# Schematic_for_AT-AT_v2.net
KiCad netlist of a schematic drawn in EAGLE
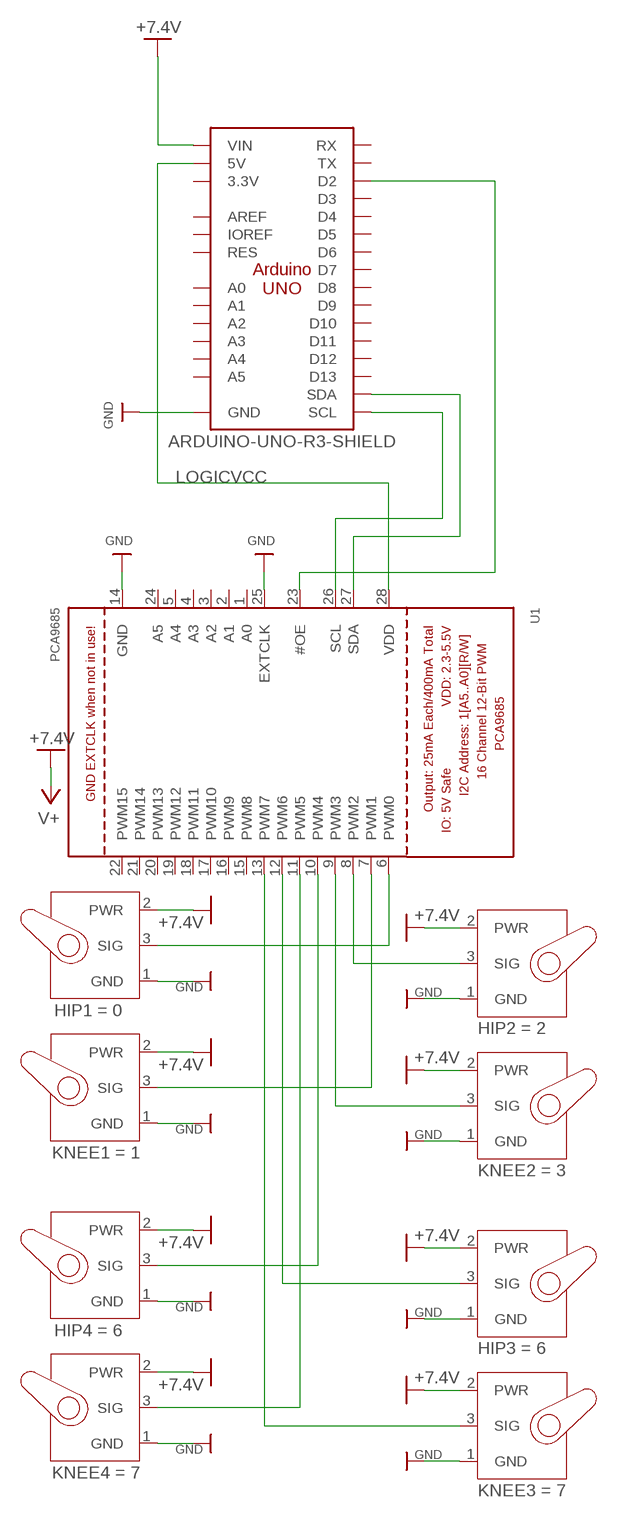
[diagram p0: schematic, sheet 1]
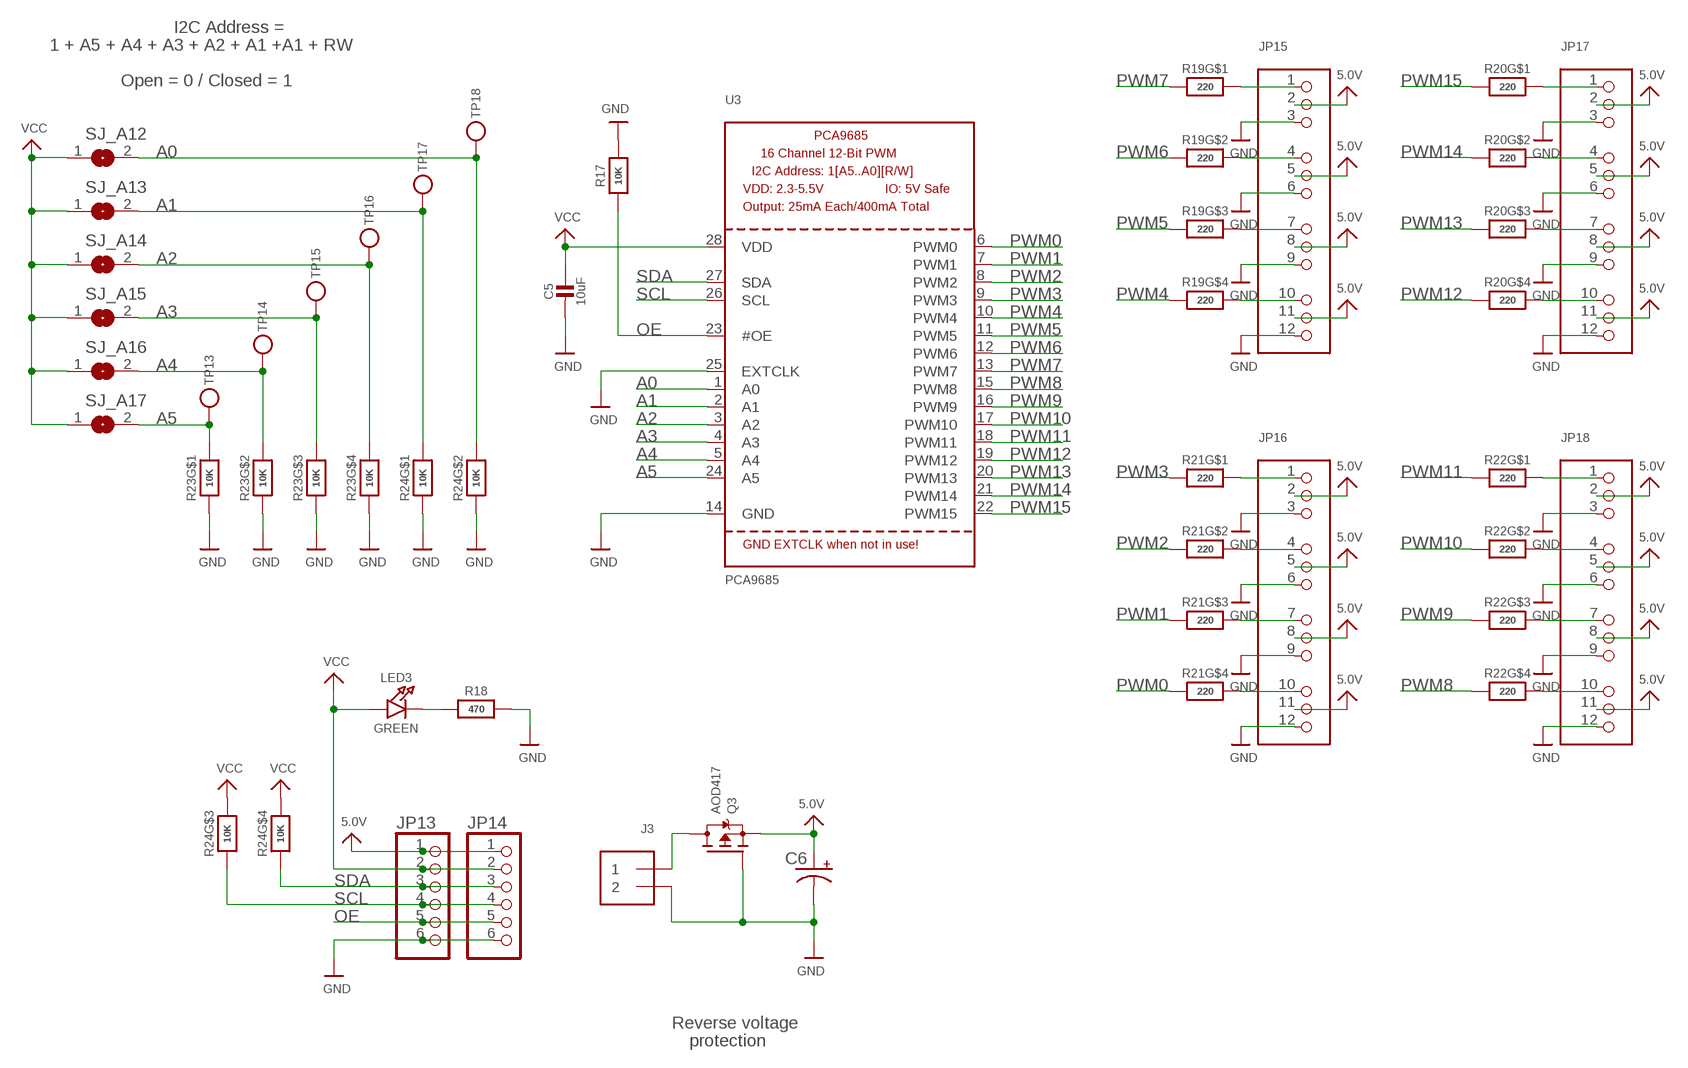
[diagram p1: schematic, sheet 2]

(export (version "E")
  (design (tool "Eeschema 10.0.6"))
  (components
    (comp (ref "U$1")
      (value "SERVOSG90-HDR")
      (footprint "eagle-import:1X03")
      (fields (field (name "HIP2") "2"))
      (libsource (lib "eagle-import") (part "SERVOSG90-HDR"))
    )
    (comp (ref "U$2")
      (value "SERVOSG90-HDR")
      (footprint "eagle-import:1X03")
      (fields (field (name "KNEE2") "3"))
      (libsource (lib "eagle-import") (part "SERVOSG90-HDR"))
    )
    (comp (ref "U$3")
      (value "SERVOSG90-HDR")
      (footprint "eagle-import:1X03")
      (fields (field (name "HIP3") "6"))
      (libsource (lib "eagle-import") (part "SERVOSG90-HDR"))
    )
    (comp (ref "U$4")
      (value "SERVOSG90-HDR")
      (footprint "eagle-import:1X03")
      (fields (field (name "KNEE3") "7"))
      (libsource (lib "eagle-import") (part "SERVOSG90-HDR"))
    )
    (comp (ref "U$5")
      (value "SERVOSG90-HDR")
      (footprint "eagle-import:1X03")
      (fields (field (name "HIP1") "0"))
      (libsource (lib "eagle-import") (part "SERVOSG90-HDR"))
    )
    (comp (ref "U$6")
      (value "SERVOSG90-HDR")
      (footprint "eagle-import:1X03")
      (fields (field (name "KNEE1") "1"))
      (libsource (lib "eagle-import") (part "SERVOSG90-HDR"))
    )
    (comp (ref "U$7")
      (value "SERVOSG90-HDR")
      (footprint "eagle-import:1X03")
      (fields (field (name "HIP4") "6"))
      (libsource (lib "eagle-import") (part "SERVOSG90-HDR"))
    )
    (comp (ref "U$8")
      (value "SERVOSG90-HDR")
      (footprint "eagle-import:1X03")
      (fields (field (name "KNEE4") "7"))
      (libsource (lib "eagle-import") (part "SERVOSG90-HDR"))
    )
    (comp (ref "U$9")
      (value "ARDUINO-UNO-R3-SHIELD")
      (footprint "eagle-import:ARDUINO-UNO-R3-SHIELD")
      (libsource (lib "eagle-import") (part "ARDUINO-UNO-R3-SHIELD"))
    )
    (comp (ref "U1")
      (value "PCA9685")
      (footprint "eagle-import:TSSOP28")
      (libsource (lib "eagle-import") (part "PCA9685"))
    )
    (comp (ref "C5")
      (value "10uF")
      (footprint "eagle-import:0805-NO")
      (libsource (lib "eagle-import") (part "CAP_CERAMIC0805-NOOUTLINE"))
    )
    (comp (ref "C6")
      (value "CPOL-USE3.5-8")
      (footprint "eagle-import:E3,5-8")
      (libsource (lib "eagle-import") (part "CPOL-USE3.5-8"))
    )
    (comp (ref "J3")
      (value "TERMBLOCK_1X2")
      (footprint "eagle-import:TERMBLOCK_1X2-3.5MM")
      (libsource (lib "eagle-import") (part "TERMBLOCK_1X2"))
    )
    (comp (ref "JP13")
      (value "PINHD-1X6CB")
      (footprint "eagle-import:1X06-CLEANBIG")
      (libsource (lib "eagle-import") (part "PINHD-1X6CB"))
    )
    (comp (ref "JP14")
      (value "PINHD-1X6CB")
      (footprint "eagle-import:1X06-CLEANBIG")
      (libsource (lib "eagle-import") (part "PINHD-1X6CB"))
    )
    (comp (ref "JP15")
      (value "HEADER-3X04")
      (footprint "eagle-import:3X04")
      (libsource (lib "eagle-import") (part "HEADER-3X04"))
    )
    (comp (ref "JP16")
      (value "HEADER-3X04")
      (footprint "eagle-import:3X04")
      (libsource (lib "eagle-import") (part "HEADER-3X04"))
    )
    (comp (ref "JP17")
      (value "HEADER-3X04")
      (footprint "eagle-import:3X04")
      (libsource (lib "eagle-import") (part "HEADER-3X04"))
    )
    (comp (ref "JP18")
      (value "HEADER-3X04")
      (footprint "eagle-import:3X04")
      (libsource (lib "eagle-import") (part "HEADER-3X04"))
    )
    (comp (ref "LED3")
      (value "GREEN")
      (footprint "eagle-import:CHIPLED_0805_NOOUTLINE")
      (libsource (lib "eagle-import") (part "LED0805_NOOUTLINE"))
    )
    (comp (ref "Q3")
      (value "AOD417")
      (footprint "eagle-import:TO252")
      (libsource (lib "eagle-import") (part "MOSFET-PTO252"))
    )
    (comp (ref "R17")
      (value "10K")
      (footprint "eagle-import:0805-NO")
      (libsource (lib "eagle-import") (part "RESISTOR0805_NOOUTLINE"))
    )
    (comp (ref "R18")
      (value "470")
      (footprint "eagle-import:_0805MP")
      (libsource (lib "eagle-import") (part "RESISTOR_0805MP"))
    )
    (comp (ref "R19")
      (value "220")
      (footprint "eagle-import:RESPACK_4X0603")
      (libsource (lib "eagle-import") (part "RESISTOR_4PACK"))
    )
    (comp (ref "R20")
      (value "220")
      (footprint "eagle-import:RESPACK_4X0603")
      (libsource (lib "eagle-import") (part "RESISTOR_4PACK"))
    )
    (comp (ref "R21")
      (value "220")
      (footprint "eagle-import:RESPACK_4X0603")
      (libsource (lib "eagle-import") (part "RESISTOR_4PACK"))
    )
    (comp (ref "R22")
      (value "220")
      (footprint "eagle-import:RESPACK_4X0603")
      (libsource (lib "eagle-import") (part "RESISTOR_4PACK"))
    )
    (comp (ref "R23")
      (value "10K")
      (footprint "eagle-import:RESPACK_4X0603")
      (libsource (lib "eagle-import") (part "RESISTOR_4PACK"))
    )
    (comp (ref "R24")
      (value "10K")
      (footprint "eagle-import:RESPACK_4X0603")
      (libsource (lib "eagle-import") (part "RESISTOR_4PACK"))
    )
    (comp (ref "SJ_A12")
      (value "SOLDERJUMPERREFLOW_NOPASTE")
      (footprint "eagle-import:SOLDERJUMPER_REFLOW_NOPASTE")
      (libsource (lib "eagle-import") (part "SOLDERJUMPERREFLOW_NOPASTE"))
    )
    (comp (ref "SJ_A13")
      (value "SOLDERJUMPERREFLOW_NOPASTE")
      (footprint "eagle-import:SOLDERJUMPER_REFLOW_NOPASTE")
      (libsource (lib "eagle-import") (part "SOLDERJUMPERREFLOW_NOPASTE"))
    )
    (comp (ref "SJ_A14")
      (value "SOLDERJUMPERREFLOW_NOPASTE")
      (footprint "eagle-import:SOLDERJUMPER_REFLOW_NOPASTE")
      (libsource (lib "eagle-import") (part "SOLDERJUMPERREFLOW_NOPASTE"))
    )
    (comp (ref "SJ_A15")
      (value "SOLDERJUMPERREFLOW_NOPASTE")
      (footprint "eagle-import:SOLDERJUMPER_REFLOW_NOPASTE")
      (libsource (lib "eagle-import") (part "SOLDERJUMPERREFLOW_NOPASTE"))
    )
    (comp (ref "SJ_A16")
      (value "SOLDERJUMPERREFLOW_NOPASTE")
      (footprint "eagle-import:SOLDERJUMPER_REFLOW_NOPASTE")
      (libsource (lib "eagle-import") (part "SOLDERJUMPERREFLOW_NOPASTE"))
    )
    (comp (ref "SJ_A17")
      (value "SOLDERJUMPERREFLOW_NOPASTE")
      (footprint "eagle-import:SOLDERJUMPER_REFLOW_NOPASTE")
      (libsource (lib "eagle-import") (part "SOLDERJUMPERREFLOW_NOPASTE"))
    )
    (comp (ref "TP13")
      (value "TESTPOINTROUND1MM")
      (footprint "eagle-import:TESTPOINT_ROUND_1MM")
      (libsource (lib "eagle-import") (part "TESTPOINTROUND1MM"))
    )
    (comp (ref "TP14")
      (value "TESTPOINTROUND1MM")
      (footprint "eagle-import:TESTPOINT_ROUND_1MM")
      (libsource (lib "eagle-import") (part "TESTPOINTROUND1MM"))
    )
    (comp (ref "TP15")
      (value "TESTPOINTROUND1MM")
      (footprint "eagle-import:TESTPOINT_ROUND_1MM")
      (libsource (lib "eagle-import") (part "TESTPOINTROUND1MM"))
    )
    (comp (ref "TP16")
      (value "TESTPOINTROUND1MM")
      (footprint "eagle-import:TESTPOINT_ROUND_1MM")
      (libsource (lib "eagle-import") (part "TESTPOINTROUND1MM"))
    )
    (comp (ref "TP17")
      (value "TESTPOINTROUND1MM")
      (footprint "eagle-import:TESTPOINT_ROUND_1MM")
      (libsource (lib "eagle-import") (part "TESTPOINTROUND1MM"))
    )
    (comp (ref "TP18")
      (value "TESTPOINTROUND1MM")
      (footprint "eagle-import:TESTPOINT_ROUND_1MM")
      (libsource (lib "eagle-import") (part "TESTPOINTROUND1MM"))
    )
    (comp (ref "U3")
      (value "PCA9685")
      (footprint "eagle-import:TSSOP28")
      (libsource (lib "eagle-import") (part "PCA9685"))
    )
  )
  (nets
    (net (code "1") (name "+7.4V") (class "Default")
      (node (ref "U$1") (pin "2") (pinfunction "PWR_2") (pintype "bidirectional"))
      (node (ref "U$2") (pin "2") (pinfunction "PWR_2") (pintype "bidirectional"))
      (node (ref "U$3") (pin "2") (pinfunction "PWR_2") (pintype "bidirectional"))
      (node (ref "U$4") (pin "2") (pinfunction "PWR_2") (pintype "bidirectional"))
      (node (ref "U$5") (pin "2") (pinfunction "PWR_2") (pintype "bidirectional"))
      (node (ref "U$6") (pin "2") (pinfunction "PWR_2") (pintype "bidirectional"))
      (node (ref "U$7") (pin "2") (pinfunction "PWR_2") (pintype "bidirectional"))
      (node (ref "U$8") (pin "2") (pinfunction "PWR_2") (pintype "bidirectional"))
      (node (ref "U$9") (pin "VIN") (pinfunction "VIN_VIN") (pintype "bidirectional"))
    )
    (net (code "2") (name "5.0V") (class "Default")
      (node (ref "C6") (pin "+") (pinfunction "+_+") (pintype "passive"))
      (node (ref "JP13") (pin "1") (pinfunction "1_1") (pintype "passive"))
      (node (ref "JP14") (pin "1") (pinfunction "1_1") (pintype "passive"))
      (node (ref "JP15") (pin "11") (pinfunction "11_11") (pintype "passive"))
      (node (ref "JP15") (pin "2") (pinfunction "2_2") (pintype "passive"))
      (node (ref "JP15") (pin "5") (pinfunction "5_5") (pintype "passive"))
      (node (ref "JP15") (pin "8") (pinfunction "8_8") (pintype "passive"))
      (node (ref "JP16") (pin "11") (pinfunction "11_11") (pintype "passive"))
      (node (ref "JP16") (pin "2") (pinfunction "2_2") (pintype "passive"))
      (node (ref "JP16") (pin "5") (pinfunction "5_5") (pintype "passive"))
      (node (ref "JP16") (pin "8") (pinfunction "8_8") (pintype "passive"))
      (node (ref "JP17") (pin "11") (pinfunction "11_11") (pintype "passive"))
      (node (ref "JP17") (pin "2") (pinfunction "2_2") (pintype "passive"))
      (node (ref "JP17") (pin "5") (pinfunction "5_5") (pintype "passive"))
      (node (ref "JP17") (pin "8") (pinfunction "8_8") (pintype "passive"))
      (node (ref "JP18") (pin "11") (pinfunction "11_11") (pintype "passive"))
      (node (ref "JP18") (pin "2") (pinfunction "2_2") (pintype "passive"))
      (node (ref "JP18") (pin "5") (pinfunction "5_5") (pintype "passive"))
      (node (ref "JP18") (pin "8") (pinfunction "8_8") (pintype "passive"))
      (node (ref "Q3") (pin "2") (pinfunction "S_2") (pintype "passive"))
    )
    (net (code "3") (name "A0") (class "Default")
      (node (ref "R24") (pin "7") (pinfunction "2_7") (pintype "passive"))
      (node (ref "SJ_A12") (pin "2") (pinfunction "2_2") (pintype "passive"))
      (node (ref "TP18") (pin "P$1") (pinfunction "P$1_P$1") (pintype "bidirectional"))
      (node (ref "U3") (pin "1") (pinfunction "A0_1") (pintype "bidirectional"))
    )
    (net (code "4") (name "A1") (class "Default")
      (node (ref "R24") (pin "8") (pinfunction "2_8") (pintype "passive"))
      (node (ref "SJ_A13") (pin "2") (pinfunction "2_2") (pintype "passive"))
      (node (ref "TP17") (pin "P$1") (pinfunction "P$1_P$1") (pintype "bidirectional"))
      (node (ref "U3") (pin "2") (pinfunction "A1_2") (pintype "bidirectional"))
    )
    (net (code "5") (name "A2") (class "Default")
      (node (ref "R23") (pin "5") (pinfunction "2_5") (pintype "passive"))
      (node (ref "SJ_A14") (pin "2") (pinfunction "2_2") (pintype "passive"))
      (node (ref "TP16") (pin "P$1") (pinfunction "P$1_P$1") (pintype "bidirectional"))
      (node (ref "U3") (pin "3") (pinfunction "A2_3") (pintype "bidirectional"))
    )
    (net (code "6") (name "A3") (class "Default")
      (node (ref "R23") (pin "6") (pinfunction "2_6") (pintype "passive"))
      (node (ref "SJ_A15") (pin "2") (pinfunction "2_2") (pintype "passive"))
      (node (ref "TP15") (pin "P$1") (pinfunction "P$1_P$1") (pintype "bidirectional"))
      (node (ref "U3") (pin "4") (pinfunction "A3_4") (pintype "bidirectional"))
    )
    (net (code "7") (name "A4") (class "Default")
      (node (ref "R23") (pin "7") (pinfunction "2_7") (pintype "passive"))
      (node (ref "SJ_A16") (pin "2") (pinfunction "2_2") (pintype "passive"))
      (node (ref "TP14") (pin "P$1") (pinfunction "P$1_P$1") (pintype "bidirectional"))
      (node (ref "U3") (pin "5") (pinfunction "A4_5") (pintype "bidirectional"))
    )
    (net (code "8") (name "A5") (class "Default")
      (node (ref "R23") (pin "8") (pinfunction "2_8") (pintype "passive"))
      (node (ref "SJ_A17") (pin "2") (pinfunction "2_2") (pintype "passive"))
      (node (ref "TP13") (pin "P$1") (pinfunction "P$1_P$1") (pintype "bidirectional"))
      (node (ref "U3") (pin "24") (pinfunction "A5_24") (pintype "bidirectional"))
    )
    (net (code "9") (name "GND") (class "Default")
      (node (ref "C5") (pin "2") (pinfunction "2_2") (pintype "passive"))
      (node (ref "C6") (pin "-") (pinfunction "-_-") (pintype "passive"))
      (node (ref "J3") (pin "2") (pinfunction "2_2") (pintype "passive"))
      (node (ref "JP13") (pin "6") (pinfunction "6_6") (pintype "passive"))
      (node (ref "JP14") (pin "6") (pinfunction "6_6") (pintype "passive"))
      (node (ref "JP15") (pin "12") (pinfunction "12_12") (pintype "passive"))
      (node (ref "JP15") (pin "3") (pinfunction "3_3") (pintype "passive"))
      (node (ref "JP15") (pin "6") (pinfunction "6_6") (pintype "passive"))
      (node (ref "JP15") (pin "9") (pinfunction "9_9") (pintype "passive"))
      (node (ref "JP16") (pin "12") (pinfunction "12_12") (pintype "passive"))
      (node (ref "JP16") (pin "3") (pinfunction "3_3") (pintype "passive"))
      (node (ref "JP16") (pin "6") (pinfunction "6_6") (pintype "passive"))
      (node (ref "JP16") (pin "9") (pinfunction "9_9") (pintype "passive"))
      (node (ref "JP17") (pin "12") (pinfunction "12_12") (pintype "passive"))
      (node (ref "JP17") (pin "3") (pinfunction "3_3") (pintype "passive"))
      (node (ref "JP17") (pin "6") (pinfunction "6_6") (pintype "passive"))
      (node (ref "JP17") (pin "9") (pinfunction "9_9") (pintype "passive"))
      (node (ref "JP18") (pin "12") (pinfunction "12_12") (pintype "passive"))
      (node (ref "JP18") (pin "3") (pinfunction "3_3") (pintype "passive"))
      (node (ref "JP18") (pin "6") (pinfunction "6_6") (pintype "passive"))
      (node (ref "JP18") (pin "9") (pinfunction "9_9") (pintype "passive"))
      (node (ref "Q3") (pin "1") (pinfunction "G_1") (pintype "passive"))
      (node (ref "R17") (pin "2") (pinfunction "2_2") (pintype "passive"))
      (node (ref "R18") (pin "2") (pinfunction "2_2") (pintype "passive"))
      (node (ref "R23") (pin "1") (pinfunction "1_1") (pintype "passive"))
      (node (ref "R23") (pin "2") (pinfunction "1_2") (pintype "passive"))
      (node (ref "R23") (pin "3") (pinfunction "1_3") (pintype "passive"))
      (node (ref "R23") (pin "4") (pinfunction "1_4") (pintype "passive"))
      (node (ref "R24") (pin "1") (pinfunction "1_1") (pintype "passive"))
      (node (ref "R24") (pin "2") (pinfunction "1_2") (pintype "passive"))
      (node (ref "U$1") (pin "1") (pinfunction "GND_1") (pintype "bidirectional"))
      (node (ref "U$2") (pin "1") (pinfunction "GND_1") (pintype "bidirectional"))
      (node (ref "U$3") (pin "1") (pinfunction "GND_1") (pintype "bidirectional"))
      (node (ref "U$4") (pin "1") (pinfunction "GND_1") (pintype "bidirectional"))
      (node (ref "U$5") (pin "1") (pinfunction "GND_1") (pintype "bidirectional"))
      (node (ref "U$6") (pin "1") (pinfunction "GND_1") (pintype "bidirectional"))
      (node (ref "U$7") (pin "1") (pinfunction "GND_1") (pintype "bidirectional"))
      (node (ref "U$8") (pin "1") (pinfunction "GND_1") (pintype "bidirectional"))
      (node (ref "U$9") (pin "GND@0") (pinfunction "GND_GND@0") (pintype "bidirectional"))
      (node (ref "U$9") (pin "GND@1") (pinfunction "GND_GND@1") (pintype "bidirectional"))
      (node (ref "U$9") (pin "GND@2") (pinfunction "GND_GND@2") (pintype "bidirectional"))
      (node (ref "U1") (pin "14") (pinfunction "GND_14") (pintype "power_in"))
      (node (ref "U1") (pin "25") (pinfunction "EXTCLK_25") (pintype "input"))
      (node (ref "U3") (pin "14") (pinfunction "GND_14") (pintype "power_in"))
      (node (ref "U3") (pin "25") (pinfunction "EXTCLK_25") (pintype "input"))
    )
    (net (code "10") (name "LOGICVCC") (class "Default")
      (node (ref "U$9") (pin "5V") (pinfunction "5V_5V") (pintype "bidirectional"))
      (node (ref "U1") (pin "28") (pinfunction "VDD_28") (pintype "power_in"))
    )
    (net (code "11") (name "Net-(LED3-PadC)") (class "Default")
      (node (ref "LED3") (pin "C") (pinfunction "C_C") (pintype "passive"))
      (node (ref "R18") (pin "1") (pinfunction "1_1") (pintype "passive"))
    )
    (net (code "12") (name "Net-(Q3-D)") (class "Default")
      (node (ref "J3") (pin "1") (pinfunction "1_1") (pintype "passive"))
      (node (ref "Q3") (pin "3") (pinfunction "D_3") (pintype "passive"))
    )
    (net (code "13") (name "Net-(R19A-2)") (class "Default")
      (node (ref "JP15") (pin "1") (pinfunction "1_1") (pintype "passive"))
      (node (ref "R19") (pin "8") (pinfunction "2_8") (pintype "passive"))
    )
    (net (code "14") (name "Net-(R19B-2)") (class "Default")
      (node (ref "JP15") (pin "4") (pinfunction "4_4") (pintype "passive"))
      (node (ref "R19") (pin "7") (pinfunction "2_7") (pintype "passive"))
    )
    (net (code "15") (name "Net-(R19C-2)") (class "Default")
      (node (ref "JP15") (pin "7") (pinfunction "7_7") (pintype "passive"))
      (node (ref "R19") (pin "6") (pinfunction "2_6") (pintype "passive"))
    )
    (net (code "16") (name "Net-(R19D-2)") (class "Default")
      (node (ref "JP15") (pin "10") (pinfunction "10_10") (pintype "passive"))
      (node (ref "R19") (pin "5") (pinfunction "2_5") (pintype "passive"))
    )
    (net (code "17") (name "Net-(R20A-2)") (class "Default")
      (node (ref "JP17") (pin "1") (pinfunction "1_1") (pintype "passive"))
      (node (ref "R20") (pin "8") (pinfunction "2_8") (pintype "passive"))
    )
    (net (code "18") (name "Net-(R20B-2)") (class "Default")
      (node (ref "JP17") (pin "4") (pinfunction "4_4") (pintype "passive"))
      (node (ref "R20") (pin "7") (pinfunction "2_7") (pintype "passive"))
    )
    (net (code "19") (name "Net-(R20C-2)") (class "Default")
      (node (ref "JP17") (pin "7") (pinfunction "7_7") (pintype "passive"))
      (node (ref "R20") (pin "6") (pinfunction "2_6") (pintype "passive"))
    )
    (net (code "20") (name "Net-(R20D-2)") (class "Default")
      (node (ref "JP17") (pin "10") (pinfunction "10_10") (pintype "passive"))
      (node (ref "R20") (pin "5") (pinfunction "2_5") (pintype "passive"))
    )
    (net (code "21") (name "Net-(R21A-2)") (class "Default")
      (node (ref "JP16") (pin "1") (pinfunction "1_1") (pintype "passive"))
      (node (ref "R21") (pin "8") (pinfunction "2_8") (pintype "passive"))
    )
    (net (code "22") (name "Net-(R21B-2)") (class "Default")
      (node (ref "JP16") (pin "4") (pinfunction "4_4") (pintype "passive"))
      (node (ref "R21") (pin "7") (pinfunction "2_7") (pintype "passive"))
    )
    (net (code "23") (name "Net-(R21C-2)") (class "Default")
      (node (ref "JP16") (pin "7") (pinfunction "7_7") (pintype "passive"))
      (node (ref "R21") (pin "6") (pinfunction "2_6") (pintype "passive"))
    )
    (net (code "24") (name "Net-(R21D-2)") (class "Default")
      (node (ref "JP16") (pin "10") (pinfunction "10_10") (pintype "passive"))
      (node (ref "R21") (pin "5") (pinfunction "2_5") (pintype "passive"))
    )
    (net (code "25") (name "Net-(R22A-2)") (class "Default")
      (node (ref "JP18") (pin "1") (pinfunction "1_1") (pintype "passive"))
      (node (ref "R22") (pin "8") (pinfunction "2_8") (pintype "passive"))
    )
    (net (code "26") (name "Net-(R22B-2)") (class "Default")
      (node (ref "JP18") (pin "4") (pinfunction "4_4") (pintype "passive"))
      (node (ref "R22") (pin "7") (pinfunction "2_7") (pintype "passive"))
    )
    (net (code "27") (name "Net-(R22C-2)") (class "Default")
      (node (ref "JP18") (pin "7") (pinfunction "7_7") (pintype "passive"))
      (node (ref "R22") (pin "6") (pinfunction "2_6") (pintype "passive"))
    )
    (net (code "28") (name "Net-(R22D-2)") (class "Default")
      (node (ref "JP18") (pin "10") (pinfunction "10_10") (pintype "passive"))
      (node (ref "R22") (pin "5") (pinfunction "2_5") (pintype "passive"))
    )
    (net (code "29") (name "Net-(U$1-SIG)") (class "Default")
      (node (ref "U$1") (pin "3") (pinfunction "SIG_3") (pintype "bidirectional"))
      (node (ref "U1") (pin "8") (pinfunction "PWM2_8") (pintype "output"))
    )
    (net (code "30") (name "Net-(U$2-SIG)") (class "Default")
      (node (ref "U$2") (pin "3") (pinfunction "SIG_3") (pintype "bidirectional"))
      (node (ref "U1") (pin "9") (pinfunction "PWM3_9") (pintype "output"))
    )
    (net (code "31") (name "Net-(U$3-SIG)") (class "Default")
      (node (ref "U$3") (pin "3") (pinfunction "SIG_3") (pintype "bidirectional"))
      (node (ref "U1") (pin "12") (pinfunction "PWM6_12") (pintype "output"))
    )
    (net (code "32") (name "Net-(U$4-SIG)") (class "Default")
      (node (ref "U$4") (pin "3") (pinfunction "SIG_3") (pintype "bidirectional"))
      (node (ref "U1") (pin "13") (pinfunction "PWM7_13") (pintype "output"))
    )
    (net (code "33") (name "Net-(U$5-SIG)") (class "Default")
      (node (ref "U$5") (pin "3") (pinfunction "SIG_3") (pintype "bidirectional"))
      (node (ref "U1") (pin "6") (pinfunction "PWM0_6") (pintype "output"))
    )
    (net (code "34") (name "Net-(U$6-SIG)") (class "Default")
      (node (ref "U$6") (pin "3") (pinfunction "SIG_3") (pintype "bidirectional"))
      (node (ref "U1") (pin "7") (pinfunction "PWM1_7") (pintype "output"))
    )
    (net (code "35") (name "Net-(U$7-SIG)") (class "Default")
      (node (ref "U$7") (pin "3") (pinfunction "SIG_3") (pintype "bidirectional"))
      (node (ref "U1") (pin "10") (pinfunction "PWM4_10") (pintype "output"))
    )
    (net (code "36") (name "Net-(U$8-SIG)") (class "Default")
      (node (ref "U$8") (pin "3") (pinfunction "SIG_3") (pintype "bidirectional"))
      (node (ref "U1") (pin "11") (pinfunction "PWM5_11") (pintype "output"))
    )
    (net (code "37") (name "Net-(U1-#OE)") (class "Default")
      (node (ref "U$9") (pin "D2") (pinfunction "D2_D2") (pintype "bidirectional"))
      (node (ref "U1") (pin "23") (pinfunction "#OE_23") (pintype "input"))
    )
    (net (code "38") (name "Net-(U1-SCL)") (class "Default")
      (node (ref "U$9") (pin "SCL") (pinfunction "SCL_SCL") (pintype "bidirectional"))
      (node (ref "U1") (pin "26") (pinfunction "SCL_26") (pintype "bidirectional"))
    )
    (net (code "39") (name "Net-(U1-SDA)") (class "Default")
      (node (ref "U$9") (pin "SDA") (pinfunction "SDA_SDA") (pintype "bidirectional"))
      (node (ref "U1") (pin "27") (pinfunction "SDA_27") (pintype "bidirectional"))
    )
    (net (code "40") (name "OE") (class "Default")
      (node (ref "JP13") (pin "5") (pinfunction "5_5") (pintype "passive"))
      (node (ref "JP14") (pin "5") (pinfunction "5_5") (pintype "passive"))
      (node (ref "R17") (pin "1") (pinfunction "1_1") (pintype "passive"))
      (node (ref "U3") (pin "23") (pinfunction "#OE_23") (pintype "input"))
    )
    (net (code "41") (name "PWM0") (class "Default")
      (node (ref "R21") (pin "4") (pinfunction "1_4") (pintype "passive"))
      (node (ref "U3") (pin "6") (pinfunction "PWM0_6") (pintype "output"))
    )
    (net (code "42") (name "PWM1") (class "Default")
      (node (ref "R21") (pin "3") (pinfunction "1_3") (pintype "passive"))
      (node (ref "U3") (pin "7") (pinfunction "PWM1_7") (pintype "output"))
    )
    (net (code "43") (name "PWM2") (class "Default")
      (node (ref "R21") (pin "2") (pinfunction "1_2") (pintype "passive"))
      (node (ref "U3") (pin "8") (pinfunction "PWM2_8") (pintype "output"))
    )
    (net (code "44") (name "PWM3") (class "Default")
      (node (ref "R21") (pin "1") (pinfunction "1_1") (pintype "passive"))
      (node (ref "U3") (pin "9") (pinfunction "PWM3_9") (pintype "output"))
    )
    (net (code "45") (name "PWM4") (class "Default")
      (node (ref "R19") (pin "4") (pinfunction "1_4") (pintype "passive"))
      (node (ref "U3") (pin "10") (pinfunction "PWM4_10") (pintype "output"))
    )
    (net (code "46") (name "PWM5") (class "Default")
      (node (ref "R19") (pin "3") (pinfunction "1_3") (pintype "passive"))
      (node (ref "U3") (pin "11") (pinfunction "PWM5_11") (pintype "output"))
    )
    (net (code "47") (name "PWM6") (class "Default")
      (node (ref "R19") (pin "2") (pinfunction "1_2") (pintype "passive"))
      (node (ref "U3") (pin "12") (pinfunction "PWM6_12") (pintype "output"))
    )
    (net (code "48") (name "PWM7") (class "Default")
      (node (ref "R19") (pin "1") (pinfunction "1_1") (pintype "passive"))
      (node (ref "U3") (pin "13") (pinfunction "PWM7_13") (pintype "output"))
    )
    (net (code "49") (name "PWM8") (class "Default")
      (node (ref "R22") (pin "4") (pinfunction "1_4") (pintype "passive"))
      (node (ref "U3") (pin "15") (pinfunction "PWM8_15") (pintype "output"))
    )
    (net (code "50") (name "PWM9") (class "Default")
      (node (ref "R22") (pin "3") (pinfunction "1_3") (pintype "passive"))
      (node (ref "U3") (pin "16") (pinfunction "PWM9_16") (pintype "output"))
    )
    (net (code "51") (name "PWM10") (class "Default")
      (node (ref "R22") (pin "2") (pinfunction "1_2") (pintype "passive"))
      (node (ref "U3") (pin "17") (pinfunction "PWM10_17") (pintype "output"))
    )
    (net (code "52") (name "PWM11") (class "Default")
      (node (ref "R22") (pin "1") (pinfunction "1_1") (pintype "passive"))
      (node (ref "U3") (pin "18") (pinfunction "PWM11_18") (pintype "output"))
    )
    (net (code "53") (name "PWM12") (class "Default")
      (node (ref "R20") (pin "4") (pinfunction "1_4") (pintype "passive"))
      (node (ref "U3") (pin "19") (pinfunction "PWM12_19") (pintype "output"))
    )
    (net (code "54") (name "PWM13") (class "Default")
      (node (ref "R20") (pin "3") (pinfunction "1_3") (pintype "passive"))
      (node (ref "U3") (pin "20") (pinfunction "PWM13_20") (pintype "output"))
    )
    (net (code "55") (name "PWM14") (class "Default")
      (node (ref "R20") (pin "2") (pinfunction "1_2") (pintype "passive"))
      (node (ref "U3") (pin "21") (pinfunction "PWM14_21") (pintype "output"))
    )
    (net (code "56") (name "PWM15") (class "Default")
      (node (ref "R20") (pin "1") (pinfunction "1_1") (pintype "passive"))
      (node (ref "U3") (pin "22") (pinfunction "PWM15_22") (pintype "output"))
    )
    (net (code "57") (name "SCL") (class "Default")
      (node (ref "JP13") (pin "4") (pinfunction "4_4") (pintype "passive"))
      (node (ref "JP14") (pin "4") (pinfunction "4_4") (pintype "passive"))
      (node (ref "R24") (pin "3") (pinfunction "1_3") (pintype "passive"))
      (node (ref "U3") (pin "26") (pinfunction "SCL_26") (pintype "bidirectional"))
    )
    (net (code "58") (name "SDA") (class "Default")
      (node (ref "JP13") (pin "3") (pinfunction "3_3") (pintype "passive"))
      (node (ref "JP14") (pin "3") (pinfunction "3_3") (pintype "passive"))
      (node (ref "R24") (pin "4") (pinfunction "1_4") (pintype "passive"))
      (node (ref "U3") (pin "27") (pinfunction "SDA_27") (pintype "bidirectional"))
    )
    (net (code "59") (name "VCC") (class "Default")
      (node (ref "C5") (pin "1") (pinfunction "1_1") (pintype "passive"))
      (node (ref "JP13") (pin "2") (pinfunction "2_2") (pintype "passive"))
      (node (ref "JP14") (pin "2") (pinfunction "2_2") (pintype "passive"))
      (node (ref "LED3") (pin "A") (pinfunction "A_A") (pintype "passive"))
      (node (ref "R24") (pin "5") (pinfunction "2_5") (pintype "passive"))
      (node (ref "R24") (pin "6") (pinfunction "2_6") (pintype "passive"))
      (node (ref "SJ_A12") (pin "1") (pinfunction "1_1") (pintype "passive"))
      (node (ref "SJ_A13") (pin "1") (pinfunction "1_1") (pintype "passive"))
      (node (ref "SJ_A14") (pin "1") (pinfunction "1_1") (pintype "passive"))
      (node (ref "SJ_A15") (pin "1") (pinfunction "1_1") (pintype "passive"))
      (node (ref "SJ_A16") (pin "1") (pinfunction "1_1") (pintype "passive"))
      (node (ref "SJ_A17") (pin "1") (pinfunction "1_1") (pintype "passive"))
      (node (ref "U3") (pin "28") (pinfunction "VDD_28") (pintype "power_in"))
    )
    (net (code "60") (name "unconnected-(U$9-Pad3.3V)") (class "Default")
      (node (ref "U$9") (pin "3.3V") (pinfunction "3.3V_3.3V") (pintype "bidirectional"))
    )
    (net (code "61") (name "unconnected-(U$9-PadA0)") (class "Default")
      (node (ref "U$9") (pin "A0") (pinfunction "A0_A0") (pintype "bidirectional"))
    )
    (net (code "62") (name "unconnected-(U$9-PadA1)") (class "Default")
      (node (ref "U$9") (pin "A1") (pinfunction "A1_A1") (pintype "bidirectional"))
    )
    (net (code "63") (name "unconnected-(U$9-PadA2)") (class "Default")
      (node (ref "U$9") (pin "A2") (pinfunction "A2_A2") (pintype "bidirectional"))
    )
    (net (code "64") (name "unconnected-(U$9-PadA3)") (class "Default")
      (node (ref "U$9") (pin "A3") (pinfunction "A3_A3") (pintype "bidirectional"))
    )
    (net (code "65") (name "unconnected-(U$9-PadA4)") (class "Default")
      (node (ref "U$9") (pin "A4") (pinfunction "A4_A4") (pintype "bidirectional"))
    )
    (net (code "66") (name "unconnected-(U$9-PadA5)") (class "Default")
      (node (ref "U$9") (pin "A5") (pinfunction "A5_A5") (pintype "bidirectional"))
    )
    (net (code "67") (name "unconnected-(U$9-PadAREF)") (class "Default")
      (node (ref "U$9") (pin "AREF") (pinfunction "AREF_AREF") (pintype "bidirectional"))
    )
    (net (code "68") (name "unconnected-(U$9-PadD3)") (class "Default")
      (node (ref "U$9") (pin "D3") (pinfunction "D3_D3") (pintype "bidirectional"))
    )
    (net (code "69") (name "unconnected-(U$9-PadD4)") (class "Default")
      (node (ref "U$9") (pin "D4") (pinfunction "D4_D4") (pintype "bidirectional"))
    )
    (net (code "70") (name "unconnected-(U$9-PadD5)") (class "Default")
      (node (ref "U$9") (pin "D5") (pinfunction "D5_D5") (pintype "bidirectional"))
    )
    (net (code "71") (name "unconnected-(U$9-PadD6)") (class "Default")
      (node (ref "U$9") (pin "D6") (pinfunction "D6_D6") (pintype "bidirectional"))
    )
    (net (code "72") (name "unconnected-(U$9-PadD7)") (class "Default")
      (node (ref "U$9") (pin "D7") (pinfunction "D7_D7") (pintype "bidirectional"))
    )
    (net (code "73") (name "unconnected-(U$9-PadD8)") (class "Default")
      (node (ref "U$9") (pin "D8") (pinfunction "D8_D8") (pintype "bidirectional"))
    )
    (net (code "74") (name "unconnected-(U$9-PadD9)") (class "Default")
      (node (ref "U$9") (pin "D9") (pinfunction "D9_D9") (pintype "bidirectional"))
    )
    (net (code "75") (name "unconnected-(U$9-PadD10)") (class "Default")
      (node (ref "U$9") (pin "D10") (pinfunction "D10_D10") (pintype "bidirectional"))
    )
    (net (code "76") (name "unconnected-(U$9-PadD11)") (class "Default")
      (node (ref "U$9") (pin "D11") (pinfunction "D11_D11") (pintype "bidirectional"))
    )
    (net (code "77") (name "unconnected-(U$9-PadD12)") (class "Default")
      (node (ref "U$9") (pin "D12") (pinfunction "D12_D12") (pintype "bidirectional"))
    )
    (net (code "78") (name "unconnected-(U$9-PadD13)") (class "Default")
      (node (ref "U$9") (pin "D13") (pinfunction "D13_D13") (pintype "bidirectional"))
    )
    (net (code "79") (name "unconnected-(U$9-PadIOREF)") (class "Default")
      (node (ref "U$9") (pin "IOREF") (pinfunction "IOREF_IOREF") (pintype "bidirectional"))
    )
    (net (code "80") (name "unconnected-(U$9-PadRES)") (class "Default")
      (node (ref "U$9") (pin "RES") (pinfunction "RES_RES") (pintype "bidirectional"))
    )
    (net (code "81") (name "unconnected-(U$9-PadRX)") (class "Default")
      (node (ref "U$9") (pin "RX") (pinfunction "RX_RX") (pintype "bidirectional"))
    )
    (net (code "82") (name "unconnected-(U$9-PadTX)") (class "Default")
      (node (ref "U$9") (pin "TX") (pinfunction "TX_TX") (pintype "bidirectional"))
    )
    (net (code "83") (name "unconnected-(U1-A0-Pad1)") (class "Default")
      (node (ref "U1") (pin "1") (pinfunction "A0_1") (pintype "bidirectional"))
    )
    (net (code "84") (name "unconnected-(U1-A1-Pad2)") (class "Default")
      (node (ref "U1") (pin "2") (pinfunction "A1_2") (pintype "bidirectional"))
    )
    (net (code "85") (name "unconnected-(U1-A2-Pad3)") (class "Default")
      (node (ref "U1") (pin "3") (pinfunction "A2_3") (pintype "bidirectional"))
    )
    (net (code "86") (name "unconnected-(U1-A3-Pad4)") (class "Default")
      (node (ref "U1") (pin "4") (pinfunction "A3_4") (pintype "bidirectional"))
    )
    (net (code "87") (name "unconnected-(U1-A4-Pad5)") (class "Default")
      (node (ref "U1") (pin "5") (pinfunction "A4_5") (pintype "bidirectional"))
    )
    (net (code "88") (name "unconnected-(U1-A5-Pad24)") (class "Default")
      (node (ref "U1") (pin "24") (pinfunction "A5_24") (pintype "bidirectional"))
    )
    (net (code "89") (name "unconnected-(U1-PWM8-Pad15)") (class "Default")
      (node (ref "U1") (pin "15") (pinfunction "PWM8_15") (pintype "output"))
    )
    (net (code "90") (name "unconnected-(U1-PWM9-Pad16)") (class "Default")
      (node (ref "U1") (pin "16") (pinfunction "PWM9_16") (pintype "output"))
    )
    (net (code "91") (name "unconnected-(U1-PWM10-Pad17)") (class "Default")
      (node (ref "U1") (pin "17") (pinfunction "PWM10_17") (pintype "output"))
    )
    (net (code "92") (name "unconnected-(U1-PWM11-Pad18)") (class "Default")
      (node (ref "U1") (pin "18") (pinfunction "PWM11_18") (pintype "output"))
    )
    (net (code "93") (name "unconnected-(U1-PWM12-Pad19)") (class "Default")
      (node (ref "U1") (pin "19") (pinfunction "PWM12_19") (pintype "output"))
    )
    (net (code "94") (name "unconnected-(U1-PWM13-Pad20)") (class "Default")
      (node (ref "U1") (pin "20") (pinfunction "PWM13_20") (pintype "output"))
    )
    (net (code "95") (name "unconnected-(U1-PWM14-Pad21)") (class "Default")
      (node (ref "U1") (pin "21") (pinfunction "PWM14_21") (pintype "output"))
    )
    (net (code "96") (name "unconnected-(U1-PWM15-Pad22)") (class "Default")
      (node (ref "U1") (pin "22") (pinfunction "PWM15_22") (pintype "output"))
    )
  )
)
